# pc_sensything_v1_3.net
KiCad netlist of a schematic drawn in EAGLE
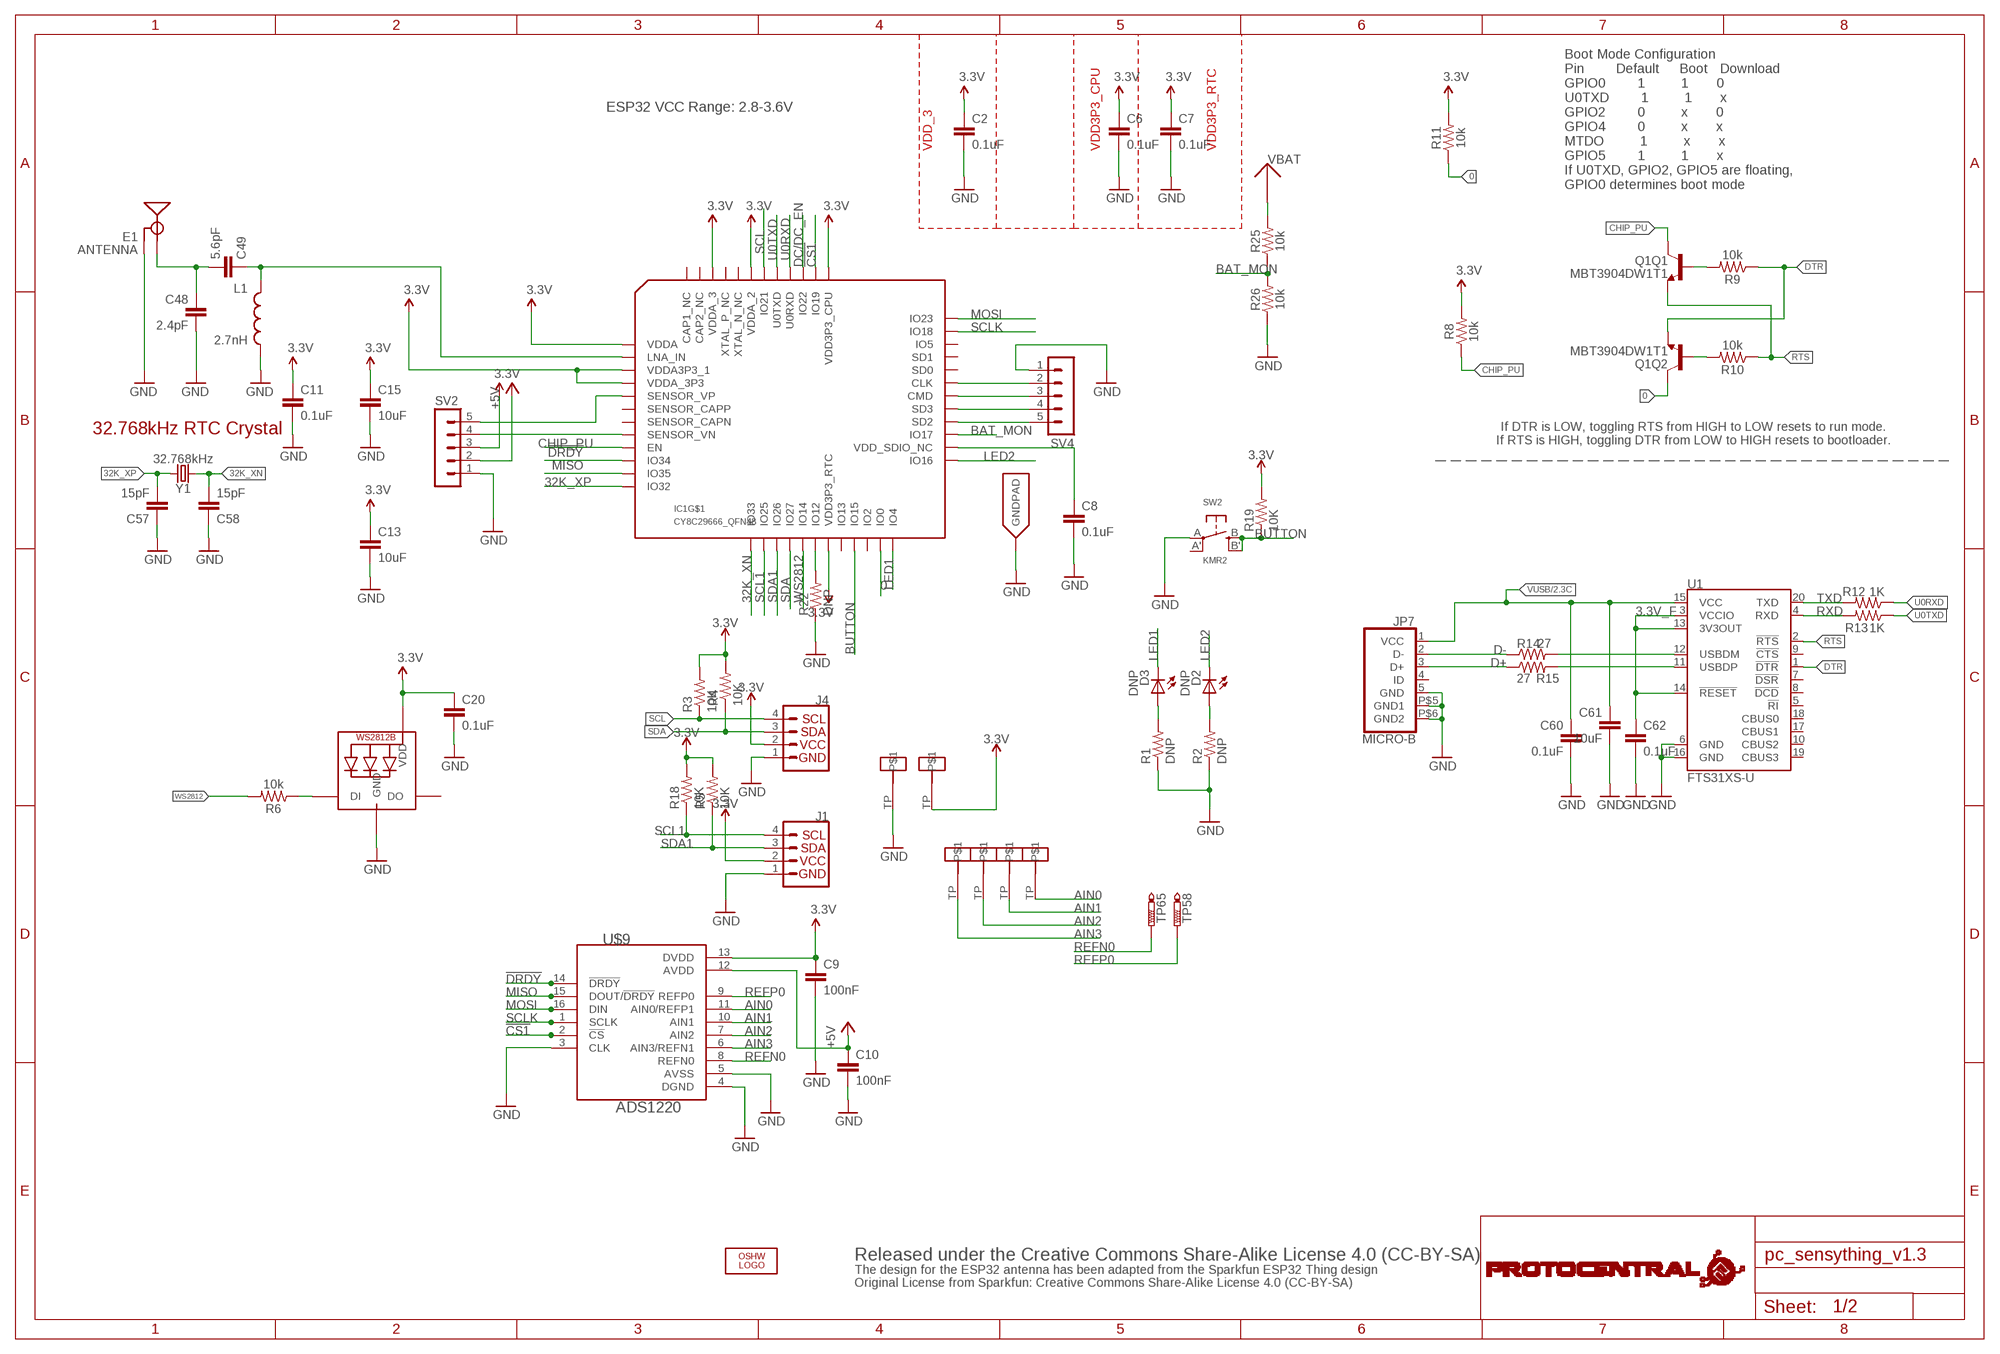
[diagram p0: schematic, sheet 1]
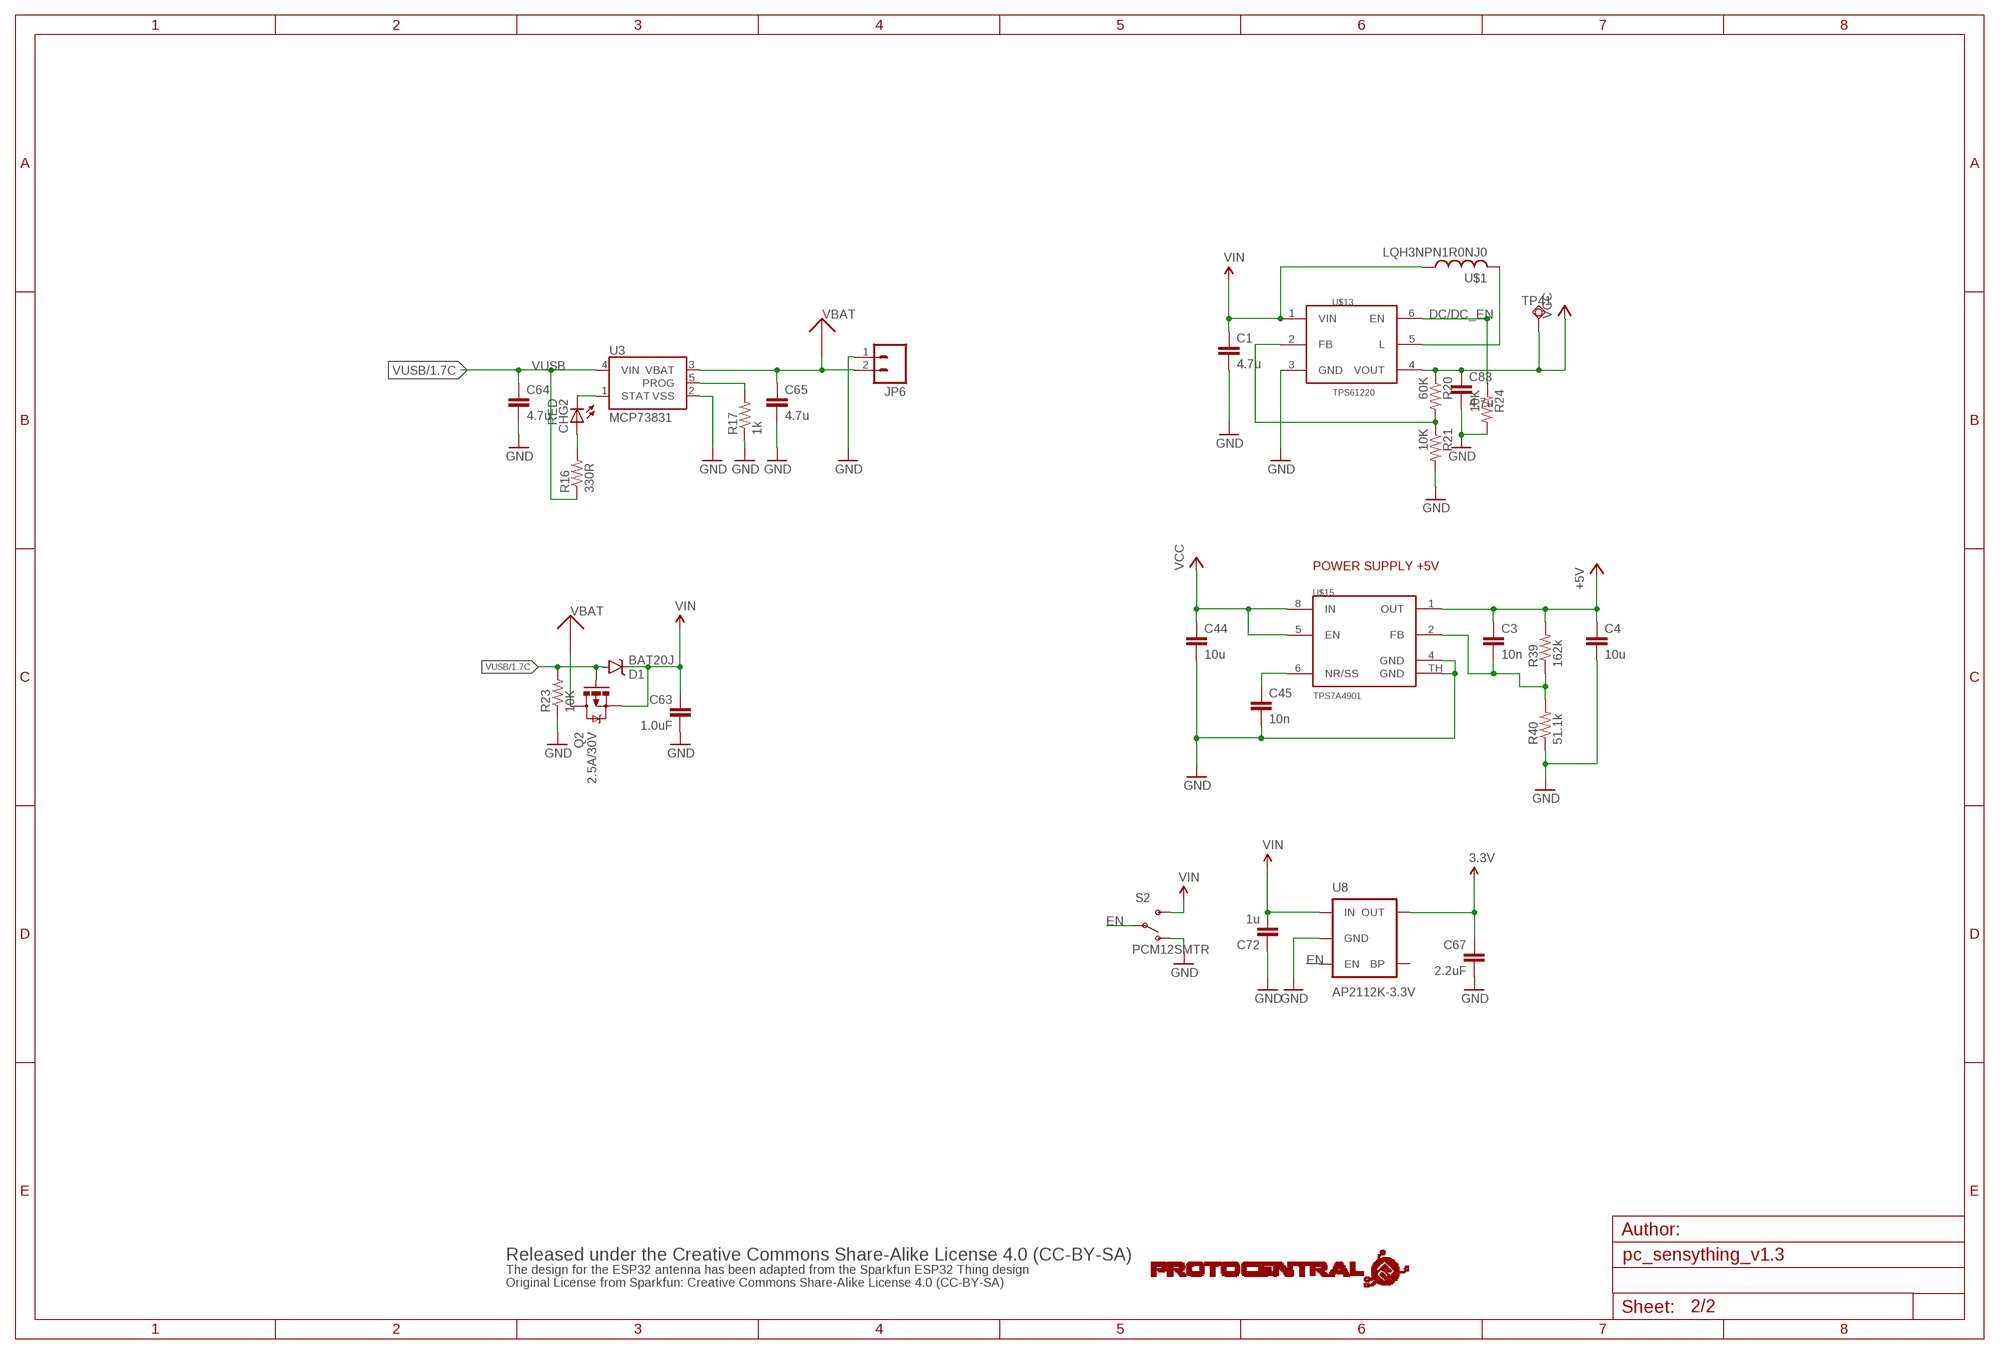
[diagram p1: schematic, sheet 2]

(export (version "E")
  (design (tool "Eeschema 10.0.6"))
  (components
    (comp (ref "C1")
      (value "4.7u")
      (footprint "eagle-import:C0805")
      (libsource (lib "eagle-import") (part "C-EUC0805"))
    )
    (comp (ref "C3")
      (value "10n")
      (footprint "eagle-import:C0402")
      (libsource (lib "eagle-import") (part "C-EUC0402"))
    )
    (comp (ref "C4")
      (value "10u")
      (footprint "eagle-import:C0805")
      (libsource (lib "eagle-import") (part "C-EUC0805"))
    )
    (comp (ref "C44")
      (value "10u")
      (footprint "eagle-import:C0805")
      (libsource (lib "eagle-import") (part "C-EUC0805"))
    )
    (comp (ref "C45")
      (value "10n")
      (footprint "eagle-import:C0402")
      (libsource (lib "eagle-import") (part "C-EUC0402"))
    )
    (comp (ref "C63")
      (value "1.0uF")
      (footprint "eagle-import:C0402")
      (libsource (lib "eagle-import") (part "C-EUC0402"))
    )
    (comp (ref "C64")
      (value "4.7u")
      (footprint "eagle-import:C0805")
      (libsource (lib "eagle-import") (part "C-EUC0805"))
    )
    (comp (ref "C65")
      (value "4.7u")
      (footprint "eagle-import:C0805")
      (libsource (lib "eagle-import") (part "C-EUC0805"))
    )
    (comp (ref "C67")
      (value "2.2uF")
      (footprint "eagle-import:C0402")
      (libsource (lib "eagle-import") (part "C-EUC0402"))
    )
    (comp (ref "C72")
      (value "1u")
      (footprint "eagle-import:C0402")
      (libsource (lib "eagle-import") (part "C-EUC0402"))
    )
    (comp (ref "C83")
      (value "4.7u")
      (footprint "eagle-import:C0805")
      (libsource (lib "eagle-import") (part "C-EUC0805"))
    )
    (comp (ref "CHG2")
      (value "RED")
      (footprint "eagle-import:CHIPLED_0603")
      (libsource (lib "eagle-import") (part "LEDCHIPLED_0603"))
    )
    (comp (ref "D1")
      (value "BAT20J")
      (footprint "eagle-import:SOD-323")
      (libsource (lib "eagle-import") (part "DIODE-SCHOTTKY-BAT20J"))
    )
    (comp (ref "JP6")
      (value "M02-JST-2MM-SMT")
      (footprint "eagle-import:JST-2-SMD")
      (libsource (lib "eagle-import") (part "M02-JST-2MM-SMT"))
    )
    (comp (ref "Q2")
      (value "2.5A/30V")
      (footprint "eagle-import:SOT23-3")
      (libsource (lib "eagle-import") (part "MOSFET-PCHANNELDMG2307L"))
    )
    (comp (ref "R16")
      (value "330R")
      (footprint "eagle-import:R0402")
      (libsource (lib "eagle-import") (part "R-US_R0402"))
    )
    (comp (ref "R17")
      (value "1k")
      (footprint "eagle-import:R0402")
      (libsource (lib "eagle-import") (part "R-US_R0402"))
    )
    (comp (ref "R20")
      (value "60K")
      (footprint "eagle-import:R0805")
      (libsource (lib "eagle-import") (part "R-US_R0805"))
    )
    (comp (ref "R21")
      (value "10K")
      (footprint "eagle-import:R0805")
      (libsource (lib "eagle-import") (part "R-US_R0805"))
    )
    (comp (ref "R23")
      (value "10K")
      (footprint "eagle-import:R0402")
      (libsource (lib "eagle-import") (part "R-US_R0402"))
    )
    (comp (ref "R24")
      (value "10K")
      (footprint "eagle-import:R0402")
      (libsource (lib "eagle-import") (part "R-US_R0402"))
    )
    (comp (ref "R39")
      (value "162k")
      (footprint "eagle-import:R0805")
      (libsource (lib "eagle-import") (part "R-US_R0805"))
    )
    (comp (ref "R40")
      (value "51.1k")
      (footprint "eagle-import:R0805")
      (libsource (lib "eagle-import") (part "R-US_R0805"))
    )
    (comp (ref "S2")
      (value "PCM12SMTR")
      (footprint "eagle-import:SWITCH-SPST-SMD-A")
      (libsource (lib "eagle-import") (part "SWITCH-SPDT-SMD-A"))
    )
    (comp (ref "TP41")
      (value "TPSQB1,27")
      (footprint "eagle-import:B1,27")
      (libsource (lib "eagle-import") (part "TPSQB1,27"))
    )
    (comp (ref "U$1")
      (value "LQH3NPN1R0NJ0")
      (footprint "eagle-import:LQH3NP")
      (libsource (lib "eagle-import") (part "LQH3NPN1R0NJ0"))
    )
    (comp (ref "U$13")
      (value "TPS61220")
      (footprint "eagle-import:SC-70-6")
      (libsource (lib "eagle-import") (part "TPS61222"))
    )
    (comp (ref "U$15")
      (value "TPS7A4901")
      (footprint "eagle-import:S-PDSO-G08")
      (libsource (lib "eagle-import") (part "TPS7A4901"))
    )
    (comp (ref "U$21")
      (value "PROTY_LOGO_WITH_TEXT")
      (footprint "eagle-import:PROTY_WITH_TEXT")
      (libsource (lib "eagle-import") (part "PROTY_LOGO_WITH_TEXT"))
    )
    (comp (ref "U3")
      (value "MCP73831")
      (footprint "eagle-import:SOT23-5")
      (libsource (lib "eagle-import") (part "MCP73831"))
    )
    (comp (ref "U8")
      (value "AP2112K-3.3V")
      (footprint "eagle-import:SOT23-5")
      (libsource (lib "eagle-import") (part "V_REG_LDOSMD"))
    )
    (comp (ref "C2")
      (value "0.1uF")
      (footprint "eagle-import:0402")
      (libsource (lib "eagle-import") (part "0.1UF-0402-16V-10%"))
    )
    (comp (ref "C6")
      (value "0.1uF")
      (footprint "eagle-import:0402")
      (libsource (lib "eagle-import") (part "0.1UF-0402-16V-10%"))
    )
    (comp (ref "C7")
      (value "0.1uF")
      (footprint "eagle-import:0402")
      (libsource (lib "eagle-import") (part "0.1UF-0402-16V-10%"))
    )
    (comp (ref "C8")
      (value "0.1uF")
      (footprint "eagle-import:0402")
      (libsource (lib "eagle-import") (part "0.1UF-0402-16V-10%"))
    )
    (comp (ref "C9")
      (value "100nF")
      (footprint "eagle-import:C0805")
      (libsource (lib "eagle-import") (part "C-EUC0805"))
    )
    (comp (ref "C10")
      (value "100nF")
      (footprint "eagle-import:C0805")
      (libsource (lib "eagle-import") (part "C-EUC0805"))
    )
    (comp (ref "C11")
      (value "0.1uF")
      (footprint "eagle-import:0402")
      (libsource (lib "eagle-import") (part "0.1UF-0402-16V-10%"))
    )
    (comp (ref "C13")
      (value "10uF")
      (footprint "eagle-import:0603")
      (libsource (lib "eagle-import") (part "10UF-0603-6.3V-20%"))
    )
    (comp (ref "C15")
      (value "10uF")
      (footprint "eagle-import:0603")
      (libsource (lib "eagle-import") (part "10UF-0603-6.3V-20%"))
    )
    (comp (ref "C20")
      (value "0.1uF")
      (footprint "eagle-import:0603")
      (libsource (lib "eagle-import") (part "0.1UF-0603-25V-(+80/-20%)"))
    )
    (comp (ref "C48")
      (value "2.4pF")
      (footprint "eagle-import:0603")
      (libsource (lib "eagle-import") (part "2.4PF-0603-50V-5%"))
    )
    (comp (ref "C49")
      (value "5.6pF")
      (footprint "eagle-import:0603")
      (libsource (lib "eagle-import") (part "5.6PF-50V-5%(0603)"))
    )
    (comp (ref "C57")
      (value "15pF")
      (footprint "eagle-import:0603")
      (libsource (lib "eagle-import") (part "15PF-0603-50V-5%"))
    )
    (comp (ref "C58")
      (value "15pF")
      (footprint "eagle-import:0603")
      (libsource (lib "eagle-import") (part "15PF-0603-50V-5%"))
    )
    (comp (ref "C60")
      (value "0.1uF")
      (footprint "eagle-import:C0402")
      (libsource (lib "eagle-import") (part "C-EUC0402"))
    )
    (comp (ref "C61")
      (value "10uF")
      (footprint "eagle-import:C0805")
      (libsource (lib "eagle-import") (part "C-EUC0805"))
    )
    (comp (ref "C62")
      (value "0.1uF")
      (footprint "eagle-import:C0402")
      (libsource (lib "eagle-import") (part "C-EUC0402"))
    )
    (comp (ref "D2")
      (value "DNP")
      (footprint "eagle-import:CHIPLED_0603")
      (libsource (lib "eagle-import") (part "LEDCHIPLED_0603"))
    )
    (comp (ref "D3")
      (value "DNP")
      (footprint "eagle-import:CHIPLED_0603")
      (libsource (lib "eagle-import") (part "LEDCHIPLED_0603"))
    )
    (comp (ref "E1")
      (value "ANTENNA")
      (footprint "eagle-import:TRACE_ANTENNA_2.4GHZ_25.7MM_TUNED")
      (libsource (lib "eagle-import") (part "ANTENNATRACE-TUNED"))
    )
    (comp (ref "IC1")
      (value "CY8C29666_QFN48")
      (footprint "eagle-import:QFN48")
      (libsource (lib "eagle-import") (part "CY8C29666_QFN48"))
    )
    (comp (ref "J1")
      (value "QWIIC_CONNECTORJS-1MM")
      (footprint "eagle-import:1X04_1MM_RA")
      (libsource (lib "eagle-import") (part "QWIIC_CONNECTORJS-1MM"))
    )
    (comp (ref "J4")
      (value "QWIIC_CONNECTORJS-1MM")
      (footprint "eagle-import:1X04_1MM_RA")
      (libsource (lib "eagle-import") (part "QWIIC_CONNECTORJS-1MM"))
    )
    (comp (ref "JP7")
      (value "MICRO-B")
      (footprint "eagle-import:MICRO-B")
      (libsource (lib "eagle-import") (part "MICRO-B"))
    )
    (comp (ref "L1")
      (value "2.7nH")
      (footprint "eagle-import:0603")
      (libsource (lib "eagle-import") (part "INDUCTOR0603"))
    )
    (comp (ref "LED1")
      (value "WS2812B5050")
      (footprint "eagle-import:WS2812B")
      (libsource (lib "eagle-import") (part "WS2812B5050"))
    )
    (comp (ref "LOGO3")
      (value "OSHW_LOGO_FILLX0200-NT")
      (footprint "eagle-import:OSHW_FILLX200_NOTEXT")
      (libsource (lib "eagle-import") (part "OSHW_LOGO_FILLX0200-NT"))
    )
    (comp (ref "Q1")
      (value "MBT3904DW1T1")
      (footprint "eagle-import:SC70-6")
      (libsource (lib "eagle-import") (part "MBT3904DW1T1"))
    )
    (comp (ref "R1")
      (value "DNP")
      (footprint "eagle-import:R0402")
      (libsource (lib "eagle-import") (part "R-US_R0402"))
    )
    (comp (ref "R2")
      (value "DNP")
      (footprint "eagle-import:R0402")
      (libsource (lib "eagle-import") (part "R-US_R0402"))
    )
    (comp (ref "R3")
      (value "10K")
      (footprint "eagle-import:R0402")
      (libsource (lib "eagle-import") (part "R-US_R0402"))
    )
    (comp (ref "R4")
      (value "10K")
      (footprint "eagle-import:R0402")
      (libsource (lib "eagle-import") (part "R-US_R0402"))
    )
    (comp (ref "R5")
      (value "10K")
      (footprint "eagle-import:R0402")
      (libsource (lib "eagle-import") (part "R-US_R0402"))
    )
    (comp (ref "R6")
      (value "10k")
      (footprint "eagle-import:0603")
      (libsource (lib "eagle-import") (part "10KOHM-1/10W-1%(0603)0603"))
    )
    (comp (ref "R8")
      (value "10k")
      (footprint "eagle-import:0603")
      (libsource (lib "eagle-import") (part "10KOHM-1/10W-1%(0603)0603"))
    )
    (comp (ref "R9")
      (value "10k")
      (footprint "eagle-import:0603")
      (libsource (lib "eagle-import") (part "10KOHM-0603-1/10W-1%"))
    )
    (comp (ref "R10")
      (value "10k")
      (footprint "eagle-import:0603")
      (libsource (lib "eagle-import") (part "10KOHM-0603-1/10W-1%"))
    )
    (comp (ref "R11")
      (value "10k")
      (footprint "eagle-import:0603")
      (libsource (lib "eagle-import") (part "10KOHM-1/10W-1%(0603)0603"))
    )
    (comp (ref "R12")
      (value "1K")
      (footprint "eagle-import:R0402")
      (libsource (lib "eagle-import") (part "R-US_R0402"))
    )
    (comp (ref "R13")
      (value "1K")
      (footprint "eagle-import:R0402")
      (libsource (lib "eagle-import") (part "R-US_R0402"))
    )
    (comp (ref "R14")
      (value "27")
      (footprint "eagle-import:R0402")
      (libsource (lib "eagle-import") (part "R-US_R0402"))
    )
    (comp (ref "R15")
      (value "27")
      (footprint "eagle-import:R0402")
      (libsource (lib "eagle-import") (part "R-US_R0402"))
    )
    (comp (ref "R18")
      (value "10K")
      (footprint "eagle-import:R0402")
      (libsource (lib "eagle-import") (part "R-US_R0402"))
    )
    (comp (ref "R19")
      (value "10K")
      (footprint "eagle-import:R0402")
      (libsource (lib "eagle-import") (part "R-US_R0402"))
    )
    (comp (ref "R22")
      (value "DNP")
      (footprint "eagle-import:R0402")
      (libsource (lib "eagle-import") (part "R-US_R0402"))
    )
    (comp (ref "R25")
      (value "10k")
      (footprint "eagle-import:0603")
      (libsource (lib "eagle-import") (part "10KOHM-1/10W-1%(0603)0603"))
    )
    (comp (ref "R26")
      (value "10k")
      (footprint "eagle-import:0603")
      (libsource (lib "eagle-import") (part "10KOHM-1/10W-1%(0603)0603"))
    )
    (comp (ref "SV2")
      (value "MA05-1")
      (footprint "eagle-import:MA05-1")
      (libsource (lib "eagle-import") (part "MA05-1"))
    )
    (comp (ref "SV4")
      (value "MA05-1")
      (footprint "eagle-import:MA05-1")
      (libsource (lib "eagle-import") (part "MA05-1"))
    )
    (comp (ref "SW2")
      (value "KMR2")
      (footprint "eagle-import:BTN_KMR2_4.6X2.8")
      (libsource (lib "eagle-import") (part "SWITCH_TACT_SMT4.6X2.8"))
    )
    (comp (ref "TP58")
      (value "PTR1PAD1-13")
      (footprint "eagle-import:P1-13")
      (libsource (lib "eagle-import") (part "PTR1PAD1-13"))
    )
    (comp (ref "TP65")
      (value "PTR1PAD1-13")
      (footprint "eagle-import:P1-13")
      (libsource (lib "eagle-import") (part "PTR1PAD1-13"))
    )
    (comp (ref "U$3")
      (value "SENSYTHING_CON")
      (footprint "eagle-import:SENSYTHING_CON")
      (libsource (lib "eagle-import") (part "SENSYTHING_CON"))
    )
    (comp (ref "U$7")
      (value "SENSYTHING_CON")
      (footprint "eagle-import:SENSYTHING_CON")
      (libsource (lib "eagle-import") (part "SENSYTHING_CON"))
    )
    (comp (ref "U$8")
      (value "SENSYTHING_CON")
      (footprint "eagle-import:SENSYTHING_CON")
      (libsource (lib "eagle-import") (part "SENSYTHING_CON"))
    )
    (comp (ref "U$9")
      (value "ADS1220")
      (footprint "eagle-import:TSSOP-16")
      (libsource (lib "eagle-import") (part "ADS1220"))
    )
    (comp (ref "U$11")
      (value "SENSYTHING_CON")
      (footprint "eagle-import:SENSYTHING_CON")
      (libsource (lib "eagle-import") (part "SENSYTHING_CON"))
    )
    (comp (ref "U$12")
      (value "SENSYTHING_CON")
      (footprint "eagle-import:SENSYTHING_CON")
      (libsource (lib "eagle-import") (part "SENSYTHING_CON"))
    )
    (comp (ref "U$14")
      (value "SENSYTHING_CON")
      (footprint "eagle-import:SENSYTHING_CON")
      (libsource (lib "eagle-import") (part "SENSYTHING_CON"))
    )
    (comp (ref "U$19")
      (value "PROTY_LOGO_WITH_TEXT")
      (footprint "eagle-import:PROTY_WITH_TEXT")
      (libsource (lib "eagle-import") (part "PROTY_LOGO_WITH_TEXT"))
    )
    (comp (ref "U1")
      (value "FTS31XS-U")
      (footprint "eagle-import:SSOP20_L")
      (libsource (lib "eagle-import") (part "FT231XS"))
    )
    (comp (ref "Y1")
      (value "32.768kHz")
      (footprint "eagle-import:CRYSTAL-SMD-3.2X1.5MM")
      (libsource (lib "eagle-import") (part "CRYSTAL-32.768KHZSMD-3.2X1.5"))
    )
  )
  (nets
    (net (code "1") (name "+5V") (class "Default")
      (node (ref "C10") (pin "1") (pinfunction "1_1") (pintype "passive"))
      (node (ref "C3") (pin "1") (pinfunction "1_1") (pintype "passive"))
      (node (ref "C4") (pin "1") (pinfunction "1_1") (pintype "passive"))
      (node (ref "R39") (pin "2") (pinfunction "2_2") (pintype "passive"))
      (node (ref "SV2") (pin "2") (pinfunction "2_2") (pintype "passive"))
      (node (ref "U$15") (pin "1") (pinfunction "OUT_1") (pintype "bidirectional"))
      (node (ref "U$9") (pin "12") (pinfunction "AVDD_12") (pintype "bidirectional"))
    )
    (net (code "2") (name "0") (class "Default")
      (node (ref "IC1") (pin "23") (pinfunction "IO0_23") (pintype "bidirectional"))
      (node (ref "Q1") (pin "6") (pinfunction "C_6") (pintype "passive"))
      (node (ref "R11") (pin "1") (pinfunction "1_1") (pintype "passive"))
    )
    (net (code "3") (name "3.3V") (class "Default")
      (node (ref "C11") (pin "1") (pinfunction "1_1") (pintype "passive"))
      (node (ref "C13") (pin "1") (pinfunction "1_1") (pintype "passive"))
      (node (ref "C15") (pin "1") (pinfunction "1_1") (pintype "passive"))
      (node (ref "C2") (pin "1") (pinfunction "1_1") (pintype "passive"))
      (node (ref "C20") (pin "1") (pinfunction "1_1") (pintype "passive"))
      (node (ref "C6") (pin "1") (pinfunction "1_1") (pintype "passive"))
      (node (ref "C67") (pin "1") (pinfunction "1_1") (pintype "passive"))
      (node (ref "C7") (pin "1") (pinfunction "1_1") (pintype "passive"))
      (node (ref "C9") (pin "1") (pinfunction "1_1") (pintype "passive"))
      (node (ref "IC1") (pin "1") (pinfunction "VDDA_1") (pintype "bidirectional"))
      (node (ref "IC1") (pin "19") (pinfunction "VDD3P3_RTC_19") (pintype "bidirectional"))
      (node (ref "IC1") (pin "3") (pinfunction "VDDA3P3_1_3") (pintype "bidirectional"))
      (node (ref "IC1") (pin "37") (pinfunction "VDD3P3_CPU_37") (pintype "bidirectional"))
      (node (ref "IC1") (pin "4") (pinfunction "VDDA_3P3_4") (pintype "bidirectional"))
      (node (ref "IC1") (pin "43") (pinfunction "VDDA_2_43") (pintype "bidirectional"))
      (node (ref "IC1") (pin "46") (pinfunction "VDDA_3_46") (pintype "bidirectional"))
      (node (ref "J1") (pin "2") (pinfunction "2_2") (pintype "power_in"))
      (node (ref "J4") (pin "2") (pinfunction "2_2") (pintype "power_in"))
      (node (ref "LED1") (pin "1-VDD") (pinfunction "VDD_1-VDD") (pintype "power_in"))
      (node (ref "R11") (pin "2") (pinfunction "2_2") (pintype "passive"))
      (node (ref "R18") (pin "2") (pinfunction "2_2") (pintype "passive"))
      (node (ref "R19") (pin "2") (pinfunction "2_2") (pintype "passive"))
      (node (ref "R3") (pin "2") (pinfunction "2_2") (pintype "passive"))
      (node (ref "R4") (pin "2") (pinfunction "2_2") (pintype "passive"))
      (node (ref "R5") (pin "2") (pinfunction "2_2") (pintype "passive"))
      (node (ref "R8") (pin "2") (pinfunction "2_2") (pintype "passive"))
      (node (ref "SV2") (pin "3") (pinfunction "3_3") (pintype "passive"))
      (node (ref "U$14") (pin "TP") (pinfunction "P$1_TP") (pintype "bidirectional"))
      (node (ref "U$9") (pin "13") (pinfunction "DVDD_13") (pintype "bidirectional"))
      (node (ref "U8") (pin "5") (pinfunction "OUT_5") (pintype "passive"))
    )
    (net (code "4") (name "3.3V_F") (class "Default")
      (node (ref "C62") (pin "1") (pinfunction "1_1") (pintype "passive"))
      (node (ref "U1") (pin "13") (pinfunction "3V3OUT_13") (pintype "bidirectional"))
      (node (ref "U1") (pin "14") (pinfunction "~{RESET}_14") (pintype "bidirectional"))
      (node (ref "U1") (pin "3") (pinfunction "VCCIO_3") (pintype "bidirectional"))
    )
    (net (code "5") (name "32K_XN") (class "Default")
      (node (ref "C58") (pin "2") (pinfunction "2_2") (pintype "passive"))
      (node (ref "IC1") (pin "13") (pinfunction "IO33_13") (pintype "bidirectional"))
      (node (ref "Y1") (pin "P$2") (pinfunction "2_P$2") (pintype "passive"))
    )
    (net (code "6") (name "32K_XP") (class "Default")
      (node (ref "C57") (pin "2") (pinfunction "2_2") (pintype "passive"))
      (node (ref "IC1") (pin "12") (pinfunction "IO32_12") (pintype "bidirectional"))
      (node (ref "Y1") (pin "P$1") (pinfunction "1_P$1") (pintype "passive"))
    )
    (net (code "7") (name "AIN0") (class "Default")
      (node (ref "U$11") (pin "TP") (pinfunction "P$1_TP") (pintype "bidirectional"))
      (node (ref "U$9") (pin "11") (pinfunction "AIN0/REFP1_11") (pintype "bidirectional"))
    )
    (net (code "8") (name "AIN1") (class "Default")
      (node (ref "U$8") (pin "TP") (pinfunction "P$1_TP") (pintype "bidirectional"))
      (node (ref "U$9") (pin "10") (pinfunction "AIN1_10") (pintype "bidirectional"))
    )
    (net (code "9") (name "AIN2") (class "Default")
      (node (ref "U$7") (pin "TP") (pinfunction "P$1_TP") (pintype "bidirectional"))
      (node (ref "U$9") (pin "7") (pinfunction "AIN2_7") (pintype "bidirectional"))
    )
    (net (code "10") (name "AIN3") (class "Default")
      (node (ref "U$3") (pin "TP") (pinfunction "P$1_TP") (pintype "bidirectional"))
      (node (ref "U$9") (pin "6") (pinfunction "AIN3/REFN1_6") (pintype "bidirectional"))
    )
    (net (code "11") (name "BAT_MON") (class "Default")
      (node (ref "IC1") (pin "27") (pinfunction "IO17_27") (pintype "bidirectional"))
      (node (ref "R25") (pin "1") (pinfunction "1_1") (pintype "passive"))
      (node (ref "R26") (pin "2") (pinfunction "2_2") (pintype "passive"))
    )
    (net (code "12") (name "BUTTON") (class "Default")
      (node (ref "IC1") (pin "21") (pinfunction "IO15_21") (pintype "bidirectional"))
      (node (ref "R19") (pin "1") (pinfunction "1_1") (pintype "passive"))
      (node (ref "SW2") (pin "B") (pinfunction "S_B") (pintype "passive"))
      (node (ref "SW2") (pin "B'") (pinfunction "S1_B'") (pintype "passive"))
    )
    (net (code "13") (name "CHIP_PU") (class "Default")
      (node (ref "IC1") (pin "9") (pinfunction "EN_9") (pintype "bidirectional"))
      (node (ref "Q1") (pin "3") (pinfunction "C_3") (pintype "passive"))
      (node (ref "R8") (pin "1") (pinfunction "1_1") (pintype "passive"))
    )
    (net (code "14") (name "D+") (class "Default")
      (node (ref "JP7") (pin "3") (pinfunction "D+_3") (pintype "bidirectional"))
      (node (ref "R15") (pin "1") (pinfunction "1_1") (pintype "passive"))
    )
    (net (code "15") (name "D-") (class "Default")
      (node (ref "JP7") (pin "2") (pinfunction "D-_2") (pintype "bidirectional"))
      (node (ref "R14") (pin "1") (pinfunction "1_1") (pintype "passive"))
    )
    (net (code "16") (name "DC{slash}DC_EN") (class "Default")
      (node (ref "IC1") (pin "39") (pinfunction "IO22_39") (pintype "bidirectional"))
      (node (ref "R24") (pin "1") (pinfunction "1_1") (pintype "passive"))
      (node (ref "U$13") (pin "6") (pinfunction "EN_6") (pintype "bidirectional"))
    )
    (net (code "17") (name "DTR") (class "Default")
      (node (ref "Q1") (pin "1") (pinfunction "E_1") (pintype "passive"))
      (node (ref "R9") (pin "1") (pinfunction "1_1") (pintype "passive"))
      (node (ref "U1") (pin "1") (pinfunction "~{DTR}_1") (pintype "bidirectional"))
    )
    (net (code "18") (name "EN") (class "Default")
      (node (ref "S2") (pin "2") (pinfunction "P_2") (pintype "passive"))
      (node (ref "U8") (pin "3") (pinfunction "EN_3") (pintype "input"))
    )
    (net (code "19") (name "GND") (class "Default")
      (node (ref "C1") (pin "2") (pinfunction "2_2") (pintype "passive"))
      (node (ref "C10") (pin "2") (pinfunction "2_2") (pintype "passive"))
      (node (ref "C11") (pin "2") (pinfunction "2_2") (pintype "passive"))
      (node (ref "C13") (pin "2") (pinfunction "2_2") (pintype "passive"))
      (node (ref "C15") (pin "2") (pinfunction "2_2") (pintype "passive"))
      (node (ref "C2") (pin "2") (pinfunction "2_2") (pintype "passive"))
      (node (ref "C20") (pin "2") (pinfunction "2_2") (pintype "passive"))
      (node (ref "C4") (pin "2") (pinfunction "2_2") (pintype "passive"))
      (node (ref "C44") (pin "2") (pinfunction "2_2") (pintype "passive"))
      (node (ref "C45") (pin "2") (pinfunction "2_2") (pintype "passive"))
      (node (ref "C48") (pin "2") (pinfunction "2_2") (pintype "passive"))
      (node (ref "C57") (pin "1") (pinfunction "1_1") (pintype "passive"))
      (node (ref "C58") (pin "1") (pinfunction "1_1") (pintype "passive"))
      (node (ref "C6") (pin "2") (pinfunction "2_2") (pintype "passive"))
      (node (ref "C60") (pin "2") (pinfunction "2_2") (pintype "passive"))
      (node (ref "C61") (pin "2") (pinfunction "2_2") (pintype "passive"))
      (node (ref "C62") (pin "2") (pinfunction "2_2") (pintype "passive"))
      (node (ref "C63") (pin "2") (pinfunction "2_2") (pintype "passive"))
      (node (ref "C64") (pin "2") (pinfunction "2_2") (pintype "passive"))
      (node (ref "C65") (pin "2") (pinfunction "2_2") (pintype "passive"))
      (node (ref "C67") (pin "2") (pinfunction "2_2") (pintype "passive"))
      (node (ref "C7") (pin "2") (pinfunction "2_2") (pintype "passive"))
      (node (ref "C72") (pin "1") (pinfunction "1_1") (pintype "passive"))
      (node (ref "C8") (pin "2") (pinfunction "2_2") (pintype "passive"))
      (node (ref "C83") (pin "2") (pinfunction "2_2") (pintype "passive"))
      (node (ref "C9") (pin "2") (pinfunction "2_2") (pintype "passive"))
      (node (ref "E1") (pin "GND") (pinfunction "GND_GND") (pintype "bidirectional"))
      (node (ref "E1") (pin "GND2") (pinfunction "GND_GND2") (pintype "bidirectional"))
      (node (ref "IC1") (pin "EXP") (pinfunction "GNDPAD_EXP") (pintype "power_in"))
      (node (ref "J1") (pin "1") (pinfunction "1_1") (pintype "power_in"))
      (node (ref "J4") (pin "1") (pinfunction "1_1") (pintype "power_in"))
      (node (ref "JP6") (pin "1") (pinfunction "1_1") (pintype "passive"))
      (node (ref "JP7") (pin "5") (pinfunction "GND_5") (pintype "bidirectional"))
      (node (ref "JP7") (pin "P$5") (pinfunction "GND1_P$5") (pintype "bidirectional"))
      (node (ref "JP7") (pin "P$6") (pinfunction "GND2_P$6") (pintype "bidirectional"))
      (node (ref "L1") (pin "2") (pinfunction "2_2") (pintype "passive"))
      (node (ref "LED1") (pin "3-GND") (pinfunction "GND_3-GND") (pintype "power_in"))
      (node (ref "R1") (pin "1") (pinfunction "1_1") (pintype "passive"))
      (node (ref "R17") (pin "1") (pinfunction "1_1") (pintype "passive"))
      (node (ref "R2") (pin "1") (pinfunction "1_1") (pintype "passive"))
      (node (ref "R21") (pin "2") (pinfunction "2_2") (pintype "passive"))
      (node (ref "R22") (pin "1") (pinfunction "1_1") (pintype "passive"))
      (node (ref "R23") (pin "1") (pinfunction "1_1") (pintype "passive"))
      (node (ref "R24") (pin "2") (pinfunction "2_2") (pintype "passive"))
      (node (ref "R26") (pin "1") (pinfunction "1_1") (pintype "passive"))
      (node (ref "R40") (pin "1") (pinfunction "1_1") (pintype "passive"))
      (node (ref "S2") (pin "1") (pinfunction "O_1") (pintype "passive"))
      (node (ref "SV2") (pin "1") (pinfunction "1_1") (pintype "passive"))
      (node (ref "SV4") (pin "1") (pinfunction "1_1") (pintype "passive"))
      (node (ref "SW2") (pin "A") (pinfunction "P_A") (pintype "passive"))
      (node (ref "U$12") (pin "TP") (pinfunction "P$1_TP") (pintype "bidirectional"))
      (node (ref "U$13") (pin "3") (pinfunction "GND_3") (pintype "bidirectional"))
      (node (ref "U$15") (pin "4") (pinfunction "GND_4") (pintype "bidirectional"))
      (node (ref "U$15") (pin "TH") (pinfunction "GND_TH") (pintype "bidirectional"))
      (node (ref "U$9") (pin "3") (pinfunction "CLK_3") (pintype "bidirectional"))
      (node (ref "U$9") (pin "4") (pinfunction "DGND_4") (pintype "bidirectional"))
      (node (ref "U$9") (pin "5") (pinfunction "AVSS_5") (pintype "bidirectional"))
      (node (ref "U1") (pin "16") (pinfunction "GND_16") (pintype "bidirectional"))
      (node (ref "U1") (pin "6") (pinfunction "GND_6") (pintype "bidirectional"))
      (node (ref "U3") (pin "2") (pinfunction "VSS_2") (pintype "power_in"))
      (node (ref "U8") (pin "2") (pinfunction "GND_2") (pintype "input"))
    )
    (net (code "20") (name "LED1") (class "Default")
      (node (ref "D3") (pin "C") (pinfunction "C_C") (pintype "passive"))
      (node (ref "IC1") (pin "24") (pinfunction "IO4_24") (pintype "bidirectional"))
    )
    (net (code "21") (name "LED2") (class "Default")
      (node (ref "D2") (pin "C") (pinfunction "C_C") (pintype "passive"))
      (node (ref "IC1") (pin "25") (pinfunction "IO16_25") (pintype "bidirectional"))
    )
    (net (code "22") (name "MISO") (class "Default")
      (node (ref "IC1") (pin "11") (pinfunction "IO35_11") (pintype "bidirectional"))
      (node (ref "U$9") (pin "15") (pinfunction "DOUT/~{DRDY}_15") (pintype "bidirectional"))
    )
    (net (code "23") (name "MOSI") (class "Default")
      (node (ref "IC1") (pin "36") (pinfunction "IO23_36") (pintype "bidirectional"))
      (node (ref "U$9") (pin "16") (pinfunction "DIN_16") (pintype "bidirectional"))
    )
    (net (code "24") (name "Net-(CHG2-PadA)") (class "Default")
      (node (ref "CHG2") (pin "A") (pinfunction "A_A") (pintype "passive"))
      (node (ref "R16") (pin "2") (pinfunction "2_2") (pintype "passive"))
    )
    (net (code "25") (name "Net-(D2-PadA)") (class "Default")
      (node (ref "D2") (pin "A") (pinfunction "A_A") (pintype "passive"))
      (node (ref "R2") (pin "2") (pinfunction "2_2") (pintype "passive"))
    )
    (net (code "26") (name "Net-(D3-PadA)") (class "Default")
      (node (ref "D3") (pin "A") (pinfunction "A_A") (pintype "passive"))
      (node (ref "R1") (pin "2") (pinfunction "2_2") (pintype "passive"))
    )
    (net (code "27") (name "Net-(E1-SIGNAL)") (class "Default")
      (node (ref "C48") (pin "1") (pinfunction "1_1") (pintype "passive"))
      (node (ref "C49") (pin "2") (pinfunction "2_2") (pintype "passive"))
      (node (ref "E1") (pin "ANT") (pinfunction "SIGNAL_ANT") (pintype "bidirectional"))
    )
    (net (code "28") (name "Net-(IC1A-CLK)") (class "Default")
      (node (ref "IC1") (pin "31") (pinfunction "CLK_31") (pintype "bidirectional"))
      (node (ref "SV4") (pin "2") (pinfunction "2_2") (pintype "passive"))
    )
    (net (code "29") (name "Net-(IC1A-CMD)") (class "Default")
      (node (ref "IC1") (pin "30") (pinfunction "CMD_30") (pintype "bidirectional"))
      (node (ref "SV4") (pin "3") (pinfunction "3_3") (pintype "passive"))
    )
    (net (code "30") (name "Net-(IC1A-IO12)") (class "Default")
      (node (ref "IC1") (pin "18") (pinfunction "IO12_18") (pintype "power_in"))
      (node (ref "R22") (pin "2") (pinfunction "2_2") (pintype "passive"))
    )
    (net (code "31") (name "Net-(IC1A-LNA_IN)") (class "Default")
      (node (ref "C49") (pin "1") (pinfunction "1_1") (pintype "passive"))
      (node (ref "IC1") (pin "2") (pinfunction "LNA_IN_2") (pintype "bidirectional"))
      (node (ref "L1") (pin "1") (pinfunction "1_1") (pintype "passive"))
    )
    (net (code "32") (name "Net-(IC1A-SD2)") (class "Default")
      (node (ref "IC1") (pin "28") (pinfunction "SD2_28") (pintype "bidirectional"))
      (node (ref "SV4") (pin "5") (pinfunction "5_5") (pintype "passive"))
    )
    (net (code "33") (name "Net-(IC1A-SD3)") (class "Default")
      (node (ref "IC1") (pin "29") (pinfunction "SD3_29") (pintype "bidirectional"))
      (node (ref "SV4") (pin "4") (pinfunction "4_4") (pintype "passive"))
    )
    (net (code "34") (name "Net-(IC1A-SENSOR_VN)") (class "Default")
      (node (ref "IC1") (pin "8") (pinfunction "SENSOR_VN_8") (pintype "bidirectional"))
      (node (ref "SV2") (pin "4") (pinfunction "4_4") (pintype "passive"))
    )
    (net (code "35") (name "Net-(IC1A-SENSOR_VP)") (class "Default")
      (node (ref "IC1") (pin "5") (pinfunction "SENSOR_VP_5") (pintype "bidirectional"))
      (node (ref "SV2") (pin "5") (pinfunction "5_5") (pintype "passive"))
    )
    (net (code "36") (name "Net-(IC1A-VDD_SDIO_NC)") (class "Default")
      (node (ref "C8") (pin "1") (pinfunction "1_1") (pintype "passive"))
      (node (ref "IC1") (pin "26") (pinfunction "VDD_SDIO_NC_26") (pintype "bidirectional"))
    )
    (net (code "37") (name "Net-(LED1-DI)") (class "Default")
      (node (ref "LED1") (pin "4-DIN") (pinfunction "DI_4-DIN") (pintype "input"))
      (node (ref "R6") (pin "1") (pinfunction "1_1") (pintype "passive"))
    )
    (net (code "38") (name "Net-(Q1A-B)") (class "Default")
      (node (ref "Q1") (pin "5") (pinfunction "B_5") (pintype "passive"))
      (node (ref "R9") (pin "2") (pinfunction "2_2") (pintype "passive"))
    )
    (net (code "39") (name "Net-(Q1B-B)") (class "Default")
      (node (ref "Q1") (pin "2") (pinfunction "B_2") (pintype "passive"))
      (node (ref "R10") (pin "2") (pinfunction "2_2") (pintype "passive"))
    )
    (net (code "40") (name "Net-(U$1-2)") (class "Default")
      (node (ref "U$1") (pin "P$2") (pinfunction "2_P$2") (pintype "passive"))
      (node (ref "U$13") (pin "5") (pinfunction "L_5") (pintype "bidirectional"))
    )
    (net (code "41") (name "Net-(U$13-FB)") (class "Default")
      (node (ref "R20") (pin "2") (pinfunction "2_2") (pintype "passive"))
      (node (ref "R21") (pin "1") (pinfunction "1_1") (pintype "passive"))
      (node (ref "U$13") (pin "2") (pinfunction "FB_2") (pintype "bidirectional"))
    )
    (net (code "42") (name "Net-(U$15-FB)") (class "Default")
      (node (ref "C3") (pin "2") (pinfunction "2_2") (pintype "passive"))
      (node (ref "R39") (pin "1") (pinfunction "1_1") (pintype "passive"))
      (node (ref "R40") (pin "2") (pinfunction "2_2") (pintype "passive"))
      (node (ref "U$15") (pin "2") (pinfunction "FB_2") (pintype "bidirectional"))
    )
    (net (code "43") (name "Net-(U$15-NR{slash}SS)") (class "Default")
      (node (ref "C45") (pin "1") (pinfunction "1_1") (pintype "passive"))
      (node (ref "U$15") (pin "6") (pinfunction "NR/SS_6") (pintype "bidirectional"))
    )
    (net (code "44") (name "Net-(U1-USBDM)") (class "Default")
      (node (ref "R14") (pin "2") (pinfunction "2_2") (pintype "passive"))
      (node (ref "U1") (pin "12") (pinfunction "USBDM_12") (pintype "bidirectional"))
    )
    (net (code "45") (name "Net-(U1-USBDP)") (class "Default")
      (node (ref "R15") (pin "2") (pinfunction "2_2") (pintype "passive"))
      (node (ref "U1") (pin "11") (pinfunction "USBDP_11") (pintype "bidirectional"))
    )
    (net (code "46") (name "Net-(U3-PROG)") (class "Default")
      (node (ref "R17") (pin "2") (pinfunction "2_2") (pintype "passive"))
      (node (ref "U3") (pin "5") (pinfunction "PROG_5") (pintype "input"))
    )
    (net (code "47") (name "Net-(U3-STAT)") (class "Default")
      (node (ref "CHG2") (pin "C") (pinfunction "C_C") (pintype "passive"))
      (node (ref "U3") (pin "1") (pinfunction "STAT_1") (pintype "output"))
    )
    (net (code "48") (name "REFN0") (class "Default")
      (node (ref "TP65") (pin "TP") (pinfunction "TP_TP") (pintype "input"))
      (node (ref "U$9") (pin "8") (pinfunction "REFN0_8") (pintype "bidirectional"))
    )
    (net (code "49") (name "REFP0") (class "Default")
      (node (ref "TP58") (pin "TP") (pinfunction "TP_TP") (pintype "input"))
      (node (ref "U$9") (pin "9") (pinfunction "REFP0_9") (pintype "bidirectional"))
    )
    (net (code "50") (name "RTS") (class "Default")
      (node (ref "Q1") (pin "4") (pinfunction "E_4") (pintype "passive"))
      (node (ref "R10") (pin "1") (pinfunction "1_1") (pintype "passive"))
      (node (ref "U1") (pin "2") (pinfunction "~{RTS}_2") (pintype "bidirectional"))
    )
    (net (code "51") (name "RXD") (class "Default")
      (node (ref "R13") (pin "2") (pinfunction "2_2") (pintype "passive"))
      (node (ref "U1") (pin "4") (pinfunction "RXD_4") (pintype "bidirectional"))
    )
    (net (code "52") (name "SCL") (class "Default")
      (node (ref "IC1") (pin "42") (pinfunction "IO21_42") (pintype "power_in"))
      (node (ref "J4") (pin "4") (pinfunction "4_4") (pintype "passive"))
      (node (ref "R3") (pin "1") (pinfunction "1_1") (pintype "passive"))
    )
    (net (code "53") (name "SCL1") (class "Default")
      (node (ref "IC1") (pin "14") (pinfunction "IO25_14") (pintype "bidirectional"))
      (node (ref "J1") (pin "4") (pinfunction "4_4") (pintype "passive"))
      (node (ref "R18") (pin "1") (pinfunction "1_1") (pintype "passive"))
    )
    (net (code "54") (name "SCLK") (class "Default")
      (node (ref "IC1") (pin "35") (pinfunction "IO18_35") (pintype "bidirectional"))
      (node (ref "U$9") (pin "1") (pinfunction "SCLK_1") (pintype "bidirectional"))
    )
    (net (code "55") (name "SDA") (class "Default")
      (node (ref "IC1") (pin "16") (pinfunction "IO27_16") (pintype "bidirectional"))
      (node (ref "J4") (pin "3") (pinfunction "3_3") (pintype "passive"))
      (node (ref "R4") (pin "1") (pinfunction "1_1") (pintype "passive"))
    )
    (net (code "56") (name "SDA1") (class "Default")
      (node (ref "IC1") (pin "15") (pinfunction "IO26_15") (pintype "bidirectional"))
      (node (ref "J1") (pin "3") (pinfunction "3_3") (pintype "passive"))
      (node (ref "R5") (pin "1") (pinfunction "1_1") (pintype "passive"))
    )
    (net (code "57") (name "SENSOR_CAPN") (class "Default")
      (node (ref "IC1") (pin "7") (pinfunction "SENSOR_CAPN_7") (pintype "power_in"))
    )
    (net (code "58") (name "TXD") (class "Default")
      (node (ref "R12") (pin "2") (pinfunction "2_2") (pintype "passive"))
      (node (ref "U1") (pin "20") (pinfunction "TXD_20") (pintype "bidirectional"))
    )
    (net (code "59") (name "U0RXD") (class "Default")
      (node (ref "IC1") (pin "40") (pinfunction "U0RXD_40") (pintype "bidirectional"))
      (node (ref "R12") (pin "1") (pinfunction "1_1") (pintype "passive"))
    )
    (net (code "60") (name "U0TXD") (class "Default")
      (node (ref "IC1") (pin "41") (pinfunction "U0TXD_41") (pintype "bidirectional"))
      (node (ref "R13") (pin "1") (pinfunction "1_1") (pintype "passive"))
    )
    (net (code "61") (name "VBAT") (class "Default")
      (node (ref "C65") (pin "1") (pinfunction "1_1") (pintype "passive"))
      (node (ref "JP6") (pin "2") (pinfunction "2_2") (pintype "passive"))
      (node (ref "Q2") (pin "3") (pinfunction "D_3") (pintype "passive"))
      (node (ref "R25") (pin "2") (pinfunction "2_2") (pintype "passive"))
      (node (ref "U3") (pin "3") (pinfunction "VBAT_3") (pintype "power_in"))
    )
    (net (code "62") (name "VCC") (class "Default")
      (node (ref "C44") (pin "1") (pinfunction "1_1") (pintype "passive"))
      (node (ref "C83") (pin "1") (pinfunction "1_1") (pintype "passive"))
      (node (ref "R20") (pin "1") (pinfunction "1_1") (pintype "passive"))
      (node (ref "TP41") (pin "TP") (pinfunction "TP_TP") (pintype "input"))
      (node (ref "U$13") (pin "4") (pinfunction "VOUT_4") (pintype "bidirectional"))
      (node (ref "U$15") (pin "5") (pinfunction "EN_5") (pintype "bidirectional"))
      (node (ref "U$15") (pin "8") (pinfunction "IN_8") (pintype "bidirectional"))
    )
    (net (code "63") (name "VIN") (class "Default")
      (node (ref "C1") (pin "1") (pinfunction "1_1") (pintype "passive"))
      (node (ref "C63") (pin "1") (pinfunction "1_1") (pintype "passive"))
      (node (ref "C72") (pin "2") (pinfunction "2_2") (pintype "passive"))
      (node (ref "D1") (pin "C") (pinfunction "C_C") (pintype "passive"))
      (node (ref "Q2") (pin "2") (pinfunction "S_2") (pintype "passive"))
      (node (ref "S2") (pin "3") (pinfunction "S_3") (pintype "passive"))
      (node (ref "U$1") (pin "P$1") (pinfunction "1_P$1") (pintype "passive"))
      (node (ref "U$13") (pin "1") (pinfunction "VIN_1") (pintype "bidirectional"))
      (node (ref "U8") (pin "1") (pinfunction "IN_1") (pintype "input"))
    )
    (net (code "64") (name "VUSB") (class "Default")
      (node (ref "C60") (pin "1") (pinfunction "1_1") (pintype "passive"))
      (node (ref "C61") (pin "1") (pinfunction "1_1") (pintype "passive"))
      (node (ref "C64") (pin "1") (pinfunction "1_1") (pintype "passive"))
      (node (ref "D1") (pin "A") (pinfunction "A_A") (pintype "passive"))
      (node (ref "JP7") (pin "1") (pinfunction "VCC_1") (pintype "bidirectional"))
      (node (ref "Q2") (pin "1") (pinfunction "G_1") (pintype "passive"))
      (node (ref "R16") (pin "1") (pinfunction "1_1") (pintype "passive"))
      (node (ref "R23") (pin "2") (pinfunction "2_2") (pintype "passive"))
      (node (ref "U1") (pin "15") (pinfunction "VCC_15") (pintype "bidirectional"))
      (node (ref "U3") (pin "4") (pinfunction "VIN_4") (pintype "power_in"))
    )
    (net (code "65") (name "WS2812") (class "Default")
      (node (ref "IC1") (pin "17") (pinfunction "IO14_17") (pintype "bidirectional"))
      (node (ref "R6") (pin "2") (pinfunction "2_2") (pintype "passive"))
    )
    (net (code "66") (name "unconnected-(IC1A-CAP1_NC-Pad48)") (class "Default")
      (node (ref "IC1") (pin "48") (pinfunction "CAP1_NC_48") (pintype "bidirectional"))
    )
    (net (code "67") (name "unconnected-(IC1A-CAP2_NC-Pad47)") (class "Default")
      (node (ref "IC1") (pin "47") (pinfunction "CAP2_NC_47") (pintype "bidirectional"))
    )
    (net (code "68") (name "unconnected-(IC1A-IO2-Pad22)") (class "Default")
      (node (ref "IC1") (pin "22") (pinfunction "IO2_22") (pintype "bidirectional"))
    )
    (net (code "69") (name "unconnected-(IC1A-IO5-Pad34)") (class "Default")
      (node (ref "IC1") (pin "34") (pinfunction "IO5_34") (pintype "bidirectional"))
    )
    (net (code "70") (name "unconnected-(IC1A-IO13-Pad20)") (class "Default")
      (node (ref "IC1") (pin "20") (pinfunction "IO13_20") (pintype "bidirectional"))
    )
    (net (code "71") (name "unconnected-(IC1A-SD0-Pad32)") (class "Default")
      (node (ref "IC1") (pin "32") (pinfunction "SD0_32") (pintype "bidirectional"))
    )
    (net (code "72") (name "unconnected-(IC1A-SD1-Pad33)") (class "Default")
      (node (ref "IC1") (pin "33") (pinfunction "SD1_33") (pintype "bidirectional"))
    )
    (net (code "73") (name "unconnected-(IC1A-SENSOR_CAPP-Pad6)") (class "Default")
      (node (ref "IC1") (pin "6") (pinfunction "SENSOR_CAPP_6") (pintype "bidirectional"))
    )
    (net (code "74") (name "unconnected-(IC1A-XTAL_N_NC-Pad44)") (class "Default")
      (node (ref "IC1") (pin "44") (pinfunction "XTAL_N_NC_44") (pintype "bidirectional"))
    )
    (net (code "75") (name "unconnected-(IC1A-XTAL_P_NC-Pad45)") (class "Default")
      (node (ref "IC1") (pin "45") (pinfunction "XTAL_P_NC_45") (pintype "bidirectional"))
    )
    (net (code "76") (name "unconnected-(JP7-ID-Pad4)") (class "Default")
      (node (ref "JP7") (pin "4") (pinfunction "ID_4") (pintype "bidirectional"))
    )
    (net (code "77") (name "unconnected-(LED1-DO-Pad2-DOUT)") (class "Default")
      (node (ref "LED1") (pin "2-DOUT") (pinfunction "DO_2-DOUT") (pintype "output"))
    )
    (net (code "78") (name "unconnected-(SW2-P1-PadA')") (class "Default")
      (node (ref "SW2") (pin "A'") (pinfunction "P1_A'") (pintype "passive"))
    )
    (net (code "79") (name "unconnected-(U1-CBUS0-Pad18)") (class "Default")
      (node (ref "U1") (pin "18") (pinfunction "CBUS0_18") (pintype "bidirectional"))
    )
    (net (code "80") (name "unconnected-(U1-CBUS1-Pad17)") (class "Default")
      (node (ref "U1") (pin "17") (pinfunction "CBUS1_17") (pintype "bidirectional"))
    )
    (net (code "81") (name "unconnected-(U1-CBUS2-Pad10)") (class "Default")
      (node (ref "U1") (pin "10") (pinfunction "CBUS2_10") (pintype "bidirectional"))
    )
    (net (code "82") (name "unconnected-(U1-CBUS3-Pad19)") (class "Default")
      (node (ref "U1") (pin "19") (pinfunction "CBUS3_19") (pintype "bidirectional"))
    )
    (net (code "83") (name "unconnected-(U1-~{CTS}-Pad9)") (class "Default")
      (node (ref "U1") (pin "9") (pinfunction "~{CTS}_9") (pintype "bidirectional"))
    )
    (net (code "84") (name "unconnected-(U1-~{DCD}-Pad8)") (class "Default")
      (node (ref "U1") (pin "8") (pinfunction "~{DCD}_8") (pintype "bidirectional"))
    )
    (net (code "85") (name "unconnected-(U1-~{DSR}-Pad7)") (class "Default")
      (node (ref "U1") (pin "7") (pinfunction "~{DSR}_7") (pintype "bidirectional"))
    )
    (net (code "86") (name "unconnected-(U1-~{RI}-Pad5)") (class "Default")
      (node (ref "U1") (pin "5") (pinfunction "~{RI}_5") (pintype "bidirectional"))
    )
    (net (code "87") (name "unconnected-(U8-BP-Pad4)") (class "Default")
      (node (ref "U8") (pin "4") (pinfunction "BP_4") (pintype "input"))
    )
    (net (code "88") (name "~{CS1}") (class "Default")
      (node (ref "IC1") (pin "38") (pinfunction "IO19_38") (pintype "bidirectional"))
      (node (ref "U$9") (pin "2") (pinfunction "~{CS}_2") (pintype "bidirectional"))
    )
    (net (code "89") (name "~{DRDY}") (class "Default")
      (node (ref "IC1") (pin "10") (pinfunction "IO34_10") (pintype "bidirectional"))
      (node (ref "U$9") (pin "14") (pinfunction "~{DRDY}_14") (pintype "bidirectional"))
    )
  )
)
